# SWP_SmartCard_NFC.net
KiCad netlist of a schematic drawn in Altium Designer
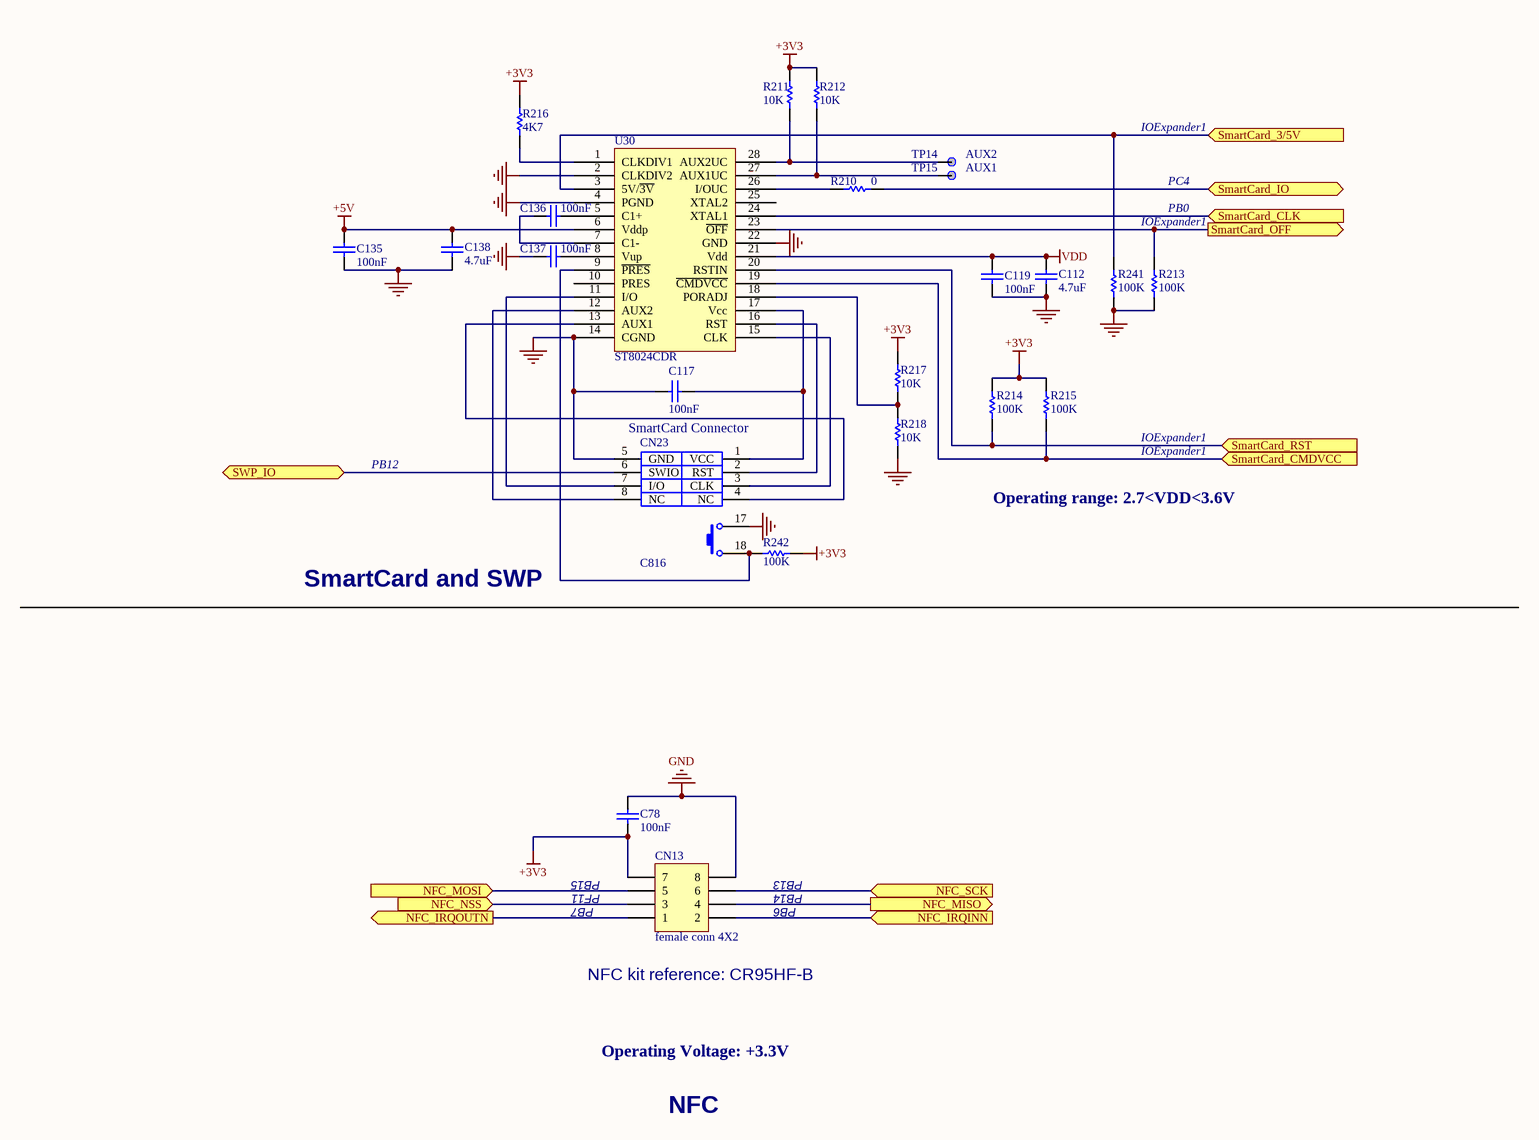
[diagram p0: SWP_SmartCard_NFC.SchDoc]

(export (version "E")
  (design (tool "Eeschema 10.0.6"))
  (components
    (comp (ref "C78")
      (value "100nF")
      (footprint "0402C")
      (description "Capacitor")
      (fields (field (name "PUBLISHER") "Altium Limited"))
      (libsource (lib "orcaeval_2") (part "CAP"))
    )
    (comp (ref "C112")
      (value "4.7uF")
      (footprint "0603C")
      (description "Capacitor")
      (fields (field (name "PUBLISHER") "Altium Limited"))
      (libsource (lib "Miscellaneous Devices") (part "Cap"))
    )
    (comp (ref "C117")
      (value "100nF")
      (footprint "0402C")
      (description "Capacitor")
      (fields (field (name "PUBLISHER") "Altium Limited"))
      (libsource (lib "Miscellaneous Devices") (part "CAP"))
    )
    (comp (ref "C119")
      (value "100nF")
      (footprint "0402C")
      (description "Capacitor")
      (fields (field (name "PUBLISHER") "Altium Limited"))
      (libsource (lib "Miscellaneous Devices") (part "CAP"))
    )
    (comp (ref "C135")
      (value "100nF")
      (footprint "0402C")
      (description "Capacitor")
      (fields (field (name "PUBLISHER") "Altium Limited"))
      (libsource (lib "Miscellaneous Devices") (part "CAP"))
    )
    (comp (ref "C136")
      (value "100nF")
      (footprint "0402C")
      (description "Capacitor")
      (fields (field (name "PUBLISHER") "Altium Limited"))
      (libsource (lib "Miscellaneous Devices") (part "CAP"))
    )
    (comp (ref "C137")
      (value "100nF")
      (footprint "0402C")
      (description "Capacitor")
      (fields (field (name "PUBLISHER") "Altium Limited"))
      (libsource (lib "Miscellaneous Devices") (part "CAP"))
    )
    (comp (ref "C138")
      (value "4.7uF")
      (footprint "0603C")
      (description "Capacitor")
      (fields (field (name "PUBLISHER") "Altium Limited"))
      (libsource (lib "Miscellaneous Devices") (part "Cap"))
    )
    (comp (ref "CN13")
      (value "female conn 4X2")
      (footprint "HDR_2X4_2R54_N")
      (description "female conn 4X2 4-Pin, Dual row")
      (fields (field (name "PUBLISHER") "Altium Limited"))
      (libsource (lib "MB1144") (part "female conn 4X2"))
    )
    (comp (ref "CN23")
      (value "C816")
      (footprint "sam_c816")
      (libsource (lib "MB1144_4") (part "Smart_card_CN"))
    )
    (comp (ref "R210")
      (value "0")
      (footprint "0603R")
      (description "Resistor")
      (fields (field (name "PUBLISHER") "Altium Limited"))
      (libsource (lib "Miscellaneous Devices") (part "Res1"))
    )
    (comp (ref "R211")
      (value "10K")
      (footprint "0402R")
      (description "Resistor")
      (fields (field (name "PUBLISHER") "Altium Limited"))
      (libsource (lib "Miscellaneous Devices") (part "Res1"))
    )
    (comp (ref "R212")
      (value "10K")
      (footprint "0402R")
      (description "Resistor")
      (fields (field (name "PUBLISHER") "Altium Limited"))
      (libsource (lib "Miscellaneous Devices") (part "Res1"))
    )
    (comp (ref "R213")
      (value "100K")
      (footprint "0402R")
      (description "Resistor")
      (fields (field (name "PUBLISHER") "Altium Limited"))
      (libsource (lib "Miscellaneous Devices") (part "Res1"))
    )
    (comp (ref "R214")
      (value "100K")
      (footprint "0402R")
      (description "Resistor")
      (fields (field (name "PUBLISHER") "Altium Limited"))
      (libsource (lib "Miscellaneous Devices") (part "Res1"))
    )
    (comp (ref "R215")
      (value "100K")
      (footprint "0402R")
      (description "Resistor")
      (fields (field (name "PUBLISHER") "Altium Limited"))
      (libsource (lib "Miscellaneous Devices") (part "Res1"))
    )
    (comp (ref "R216")
      (value "4K7")
      (footprint "0402R")
      (description "Resistor")
      (fields (field (name "PUBLISHER") "Altium Limited"))
      (libsource (lib "Miscellaneous Devices") (part "Res1"))
    )
    (comp (ref "R217")
      (value "10K")
      (footprint "0402R")
      (description "Resistor")
      (fields (field (name "PUBLISHER") "Altium Limited"))
      (libsource (lib "Miscellaneous Devices") (part "Res1"))
    )
    (comp (ref "R218")
      (value "10K")
      (footprint "0402R")
      (description "Resistor")
      (fields (field (name "PUBLISHER") "Altium Limited"))
      (libsource (lib "Miscellaneous Devices") (part "Res1"))
    )
    (comp (ref "R241")
      (value "100K")
      (footprint "0402R")
      (description "Resistor")
      (fields (field (name "PUBLISHER") "Altium Limited"))
      (libsource (lib "Miscellaneous Devices") (part "Res1"))
    )
    (comp (ref "R242")
      (value "100K")
      (footprint "0402R")
      (description "Resistor")
      (fields (field (name "PUBLISHER") "Altium Limited"))
      (libsource (lib "Miscellaneous Devices") (part "Res1"))
    )
    (comp (ref "TP14")
      (value "[N/A]")
      (footprint "TP")
      (fields (field (name "TP NAME") "AUX2"))
      (libsource (lib "*") (part "TP"))
    )
    (comp (ref "TP15")
      (value "[N/A]")
      (footprint "TP")
      (fields (field (name "TP NAME") "AUX1"))
      (libsource (lib "*") (part "TP"))
    )
    (comp (ref "U30")
      (value "ST8024CDR")
      (footprint "SOIC28W_1R27_17R9X10R325")
      (libsource (lib "MB525") (part "ST8024CTR"))
    )
  )
  (nets
    (net (code "1") (name "+3V3") (class "Default")
      (node (ref "C78") (pin "2") (pinfunction "2_2") (pintype "passive"))
      (node (ref "CN13") (pin "7") (pinfunction "7_7") (pintype "passive"))
      (node (ref "R211") (pin "1") (pinfunction "1_1") (pintype "passive"))
      (node (ref "R212") (pin "1") (pinfunction "1_1") (pintype "passive"))
      (node (ref "R214") (pin "1") (pinfunction "1_1") (pintype "passive"))
      (node (ref "R215") (pin "1") (pinfunction "1_1") (pintype "passive"))
      (node (ref "R216") (pin "1") (pinfunction "1_1") (pintype "passive"))
      (node (ref "R217") (pin "1") (pinfunction "1_1") (pintype "passive"))
      (node (ref "R242") (pin "1") (pinfunction "1_1") (pintype "passive"))
    )
    (net (code "2") (name "+5V") (class "Default")
      (node (ref "C135") (pin "1") (pinfunction "1_1") (pintype "passive"))
      (node (ref "C138") (pin "1") (pinfunction "1_1") (pintype "passive"))
      (node (ref "U30") (pin "6") (pinfunction "Vddp_6") (pintype "passive"))
    )
    (net (code "3") (name "/NFC_IRQINN") (class "Default")
      (node (ref "CN13") (pin "2") (pinfunction "2_2") (pintype "passive"))
    )
    (net (code "4") (name "/NFC_IRQOUTN") (class "Default")
      (node (ref "CN13") (pin "1") (pinfunction "1_1") (pintype "passive"))
    )
    (net (code "5") (name "/NFC_MISO") (class "Default")
      (node (ref "CN13") (pin "4") (pinfunction "4_4") (pintype "passive"))
    )
    (net (code "6") (name "/NFC_MOSI") (class "Default")
      (node (ref "CN13") (pin "5") (pinfunction "5_5") (pintype "passive"))
    )
    (net (code "7") (name "/NFC_NSS") (class "Default")
      (node (ref "CN13") (pin "3") (pinfunction "3_3") (pintype "passive"))
    )
    (net (code "8") (name "/NFC_SCK") (class "Default")
      (node (ref "CN13") (pin "6") (pinfunction "6_6") (pintype "passive"))
    )
    (net (code "9") (name "/SWP_IO") (class "Default")
      (node (ref "CN23") (pin "6") (pinfunction "SWIO_6") (pintype "passive"))
    )
    (net (code "10") (name "/SmartCard_3{slash}5V") (class "Default")
      (node (ref "R241") (pin "1") (pinfunction "1_1") (pintype "passive"))
      (node (ref "U30") (pin "3") (pinfunction "5V/~{3V}_3") (pintype "passive"))
    )
    (net (code "11") (name "/SmartCard_CLK") (class "Default")
      (node (ref "U30") (pin "24") (pinfunction "XTAL1_24") (pintype "passive"))
    )
    (net (code "12") (name "/SmartCard_CMDVCC") (class "Default")
      (node (ref "R215") (pin "2") (pinfunction "2_2") (pintype "passive"))
      (node (ref "U30") (pin "19") (pinfunction "~{CMDVCC}_19") (pintype "passive"))
    )
    (net (code "13") (name "/SmartCard_IO") (class "Default")
      (node (ref "R210") (pin "2") (pinfunction "2_2") (pintype "passive"))
    )
    (net (code "14") (name "/SmartCard_OFF") (class "Default")
      (node (ref "R213") (pin "1") (pinfunction "1_1") (pintype "passive"))
      (node (ref "U30") (pin "23") (pinfunction "~{OFF}_23") (pintype "passive"))
    )
    (net (code "15") (name "/SmartCard_RST") (class "Default")
      (node (ref "R214") (pin "2") (pinfunction "2_2") (pintype "passive"))
      (node (ref "U30") (pin "20") (pinfunction "RSTIN_20") (pintype "passive"))
    )
    (net (code "16") (name "GND") (class "Default")
      (node (ref "C112") (pin "2") (pinfunction "2_2") (pintype "passive"))
      (node (ref "C117") (pin "1") (pinfunction "1_1") (pintype "passive"))
      (node (ref "C119") (pin "2") (pinfunction "2_2") (pintype "passive"))
      (node (ref "C135") (pin "2") (pinfunction "2_2") (pintype "passive"))
      (node (ref "C137") (pin "2") (pinfunction "2_2") (pintype "passive"))
      (node (ref "C138") (pin "2") (pinfunction "2_2") (pintype "passive"))
      (node (ref "C78") (pin "1") (pinfunction "1_1") (pintype "passive"))
      (node (ref "CN13") (pin "8") (pinfunction "8_8") (pintype "passive"))
      (node (ref "CN23") (pin "17") (pintype "passive"))
      (node (ref "CN23") (pin "5") (pinfunction "GND_5") (pintype "passive"))
      (node (ref "R213") (pin "2") (pinfunction "2_2") (pintype "passive"))
      (node (ref "R218") (pin "2") (pinfunction "2_2") (pintype "passive"))
      (node (ref "R241") (pin "2") (pinfunction "2_2") (pintype "passive"))
      (node (ref "U30") (pin "14") (pinfunction "CGND_14") (pintype "passive"))
      (node (ref "U30") (pin "2") (pinfunction "CLKDIV2_2") (pintype "passive"))
      (node (ref "U30") (pin "22") (pinfunction "GND_22") (pintype "passive"))
      (node (ref "U30") (pin "4") (pinfunction "PGND_4") (pintype "passive"))
    )
    (net (code "17") (name "Net-(CN23-CLK)") (class "Default")
      (node (ref "CN23") (pin "3") (pinfunction "CLK_3") (pintype "passive"))
      (node (ref "U30") (pin "15") (pinfunction "CLK_15") (pintype "passive"))
    )
    (net (code "18") (name "Net-(CN23-I{slash}O)") (class "Default")
      (node (ref "CN23") (pin "7") (pinfunction "I/O_7") (pintype "passive"))
      (node (ref "U30") (pin "11") (pinfunction "I/O_11") (pintype "passive"))
    )
    (net (code "19") (name "Net-(CN23-RST)") (class "Default")
      (node (ref "CN23") (pin "2") (pinfunction "RST_2") (pintype "passive"))
      (node (ref "U30") (pin "16") (pinfunction "RST_16") (pintype "passive"))
    )
    (net (code "20") (name "Net-(CN23-VCC)") (class "Default")
      (node (ref "C117") (pin "2") (pinfunction "2_2") (pintype "passive"))
      (node (ref "CN23") (pin "1") (pinfunction "VCC_1") (pintype "passive"))
      (node (ref "U30") (pin "17") (pinfunction "Vcc_17") (pintype "passive"))
    )
    (net (code "21") (name "Net-(U30-AUX1)") (class "Default")
      (node (ref "CN23") (pin "4") (pinfunction "NC_4") (pintype "passive"))
      (node (ref "U30") (pin "13") (pinfunction "AUX1_13") (pintype "passive"))
    )
    (net (code "22") (name "Net-(U30-AUX1UC)") (class "Default")
      (node (ref "R212") (pin "2") (pinfunction "2_2") (pintype "passive"))
      (node (ref "TP15") (pin "1") (pinfunction "1_1") (pintype "passive"))
      (node (ref "U30") (pin "27") (pinfunction "AUX1UC_27") (pintype "passive"))
    )
    (net (code "23") (name "Net-(U30-AUX2)") (class "Default")
      (node (ref "CN23") (pin "8") (pinfunction "NC_8") (pintype "passive"))
      (node (ref "U30") (pin "12") (pinfunction "AUX2_12") (pintype "passive"))
    )
    (net (code "24") (name "Net-(U30-AUX2UC)") (class "Default")
      (node (ref "R211") (pin "2") (pinfunction "2_2") (pintype "passive"))
      (node (ref "TP14") (pin "1") (pinfunction "1_1") (pintype "passive"))
      (node (ref "U30") (pin "28") (pinfunction "AUX2UC_28") (pintype "passive"))
    )
    (net (code "25") (name "Net-(U30-C1+)") (class "Default")
      (node (ref "C136") (pin "2") (pinfunction "2_2") (pintype "passive"))
      (node (ref "U30") (pin "5") (pinfunction "C1+_5") (pintype "passive"))
    )
    (net (code "26") (name "Net-(U30-C1-)") (class "Default")
      (node (ref "C136") (pin "1") (pinfunction "1_1") (pintype "passive"))
      (node (ref "U30") (pin "7") (pinfunction "C1-_7") (pintype "passive"))
    )
    (net (code "27") (name "Net-(U30-CLKDIV1)") (class "Default")
      (node (ref "R216") (pin "2") (pinfunction "2_2") (pintype "passive"))
      (node (ref "U30") (pin "1") (pinfunction "CLKDIV1_1") (pintype "passive"))
    )
    (net (code "28") (name "Net-(U30-I{slash}OUC)") (class "Default")
      (node (ref "R210") (pin "1") (pinfunction "1_1") (pintype "passive"))
      (node (ref "U30") (pin "26") (pinfunction "I/OUC_26") (pintype "passive"))
    )
    (net (code "29") (name "Net-(U30-PORADJ)") (class "Default")
      (node (ref "R217") (pin "2") (pinfunction "2_2") (pintype "passive"))
      (node (ref "R218") (pin "1") (pinfunction "1_1") (pintype "passive"))
      (node (ref "U30") (pin "18") (pinfunction "PORADJ_18") (pintype "passive"))
    )
    (net (code "30") (name "Net-(U30-Vup)") (class "Default")
      (node (ref "C137") (pin "1") (pinfunction "1_1") (pintype "passive"))
      (node (ref "U30") (pin "8") (pinfunction "Vup_8") (pintype "passive"))
    )
    (net (code "31") (name "Net-(U30-~{PRES})") (class "Default")
      (node (ref "CN23") (pin "18") (pintype "passive"))
      (node (ref "R242") (pin "2") (pinfunction "2_2") (pintype "passive"))
      (node (ref "U30") (pin "9") (pinfunction "~{PRES}_9") (pintype "passive"))
    )
    (net (code "32") (name "VDD") (class "Default")
      (node (ref "C112") (pin "1") (pinfunction "1_1") (pintype "passive"))
      (node (ref "C119") (pin "1") (pinfunction "1_1") (pintype "passive"))
      (node (ref "U30") (pin "21") (pinfunction "Vdd_21") (pintype "passive"))
    )
    (net (code "33") (name "unconnected-(U30-PRES-Pad10)") (class "Default")
      (node (ref "U30") (pin "10") (pinfunction "PRES_10") (pintype "passive"))
    )
    (net (code "34") (name "unconnected-(U30-XTAL2-Pad25)") (class "Default")
      (node (ref "U30") (pin "25") (pinfunction "XTAL2_25") (pintype "passive"))
    )
  )
)
